# final_sensor_sch_v3.net
KiCad netlist of a schematic drawn in Altium Designer
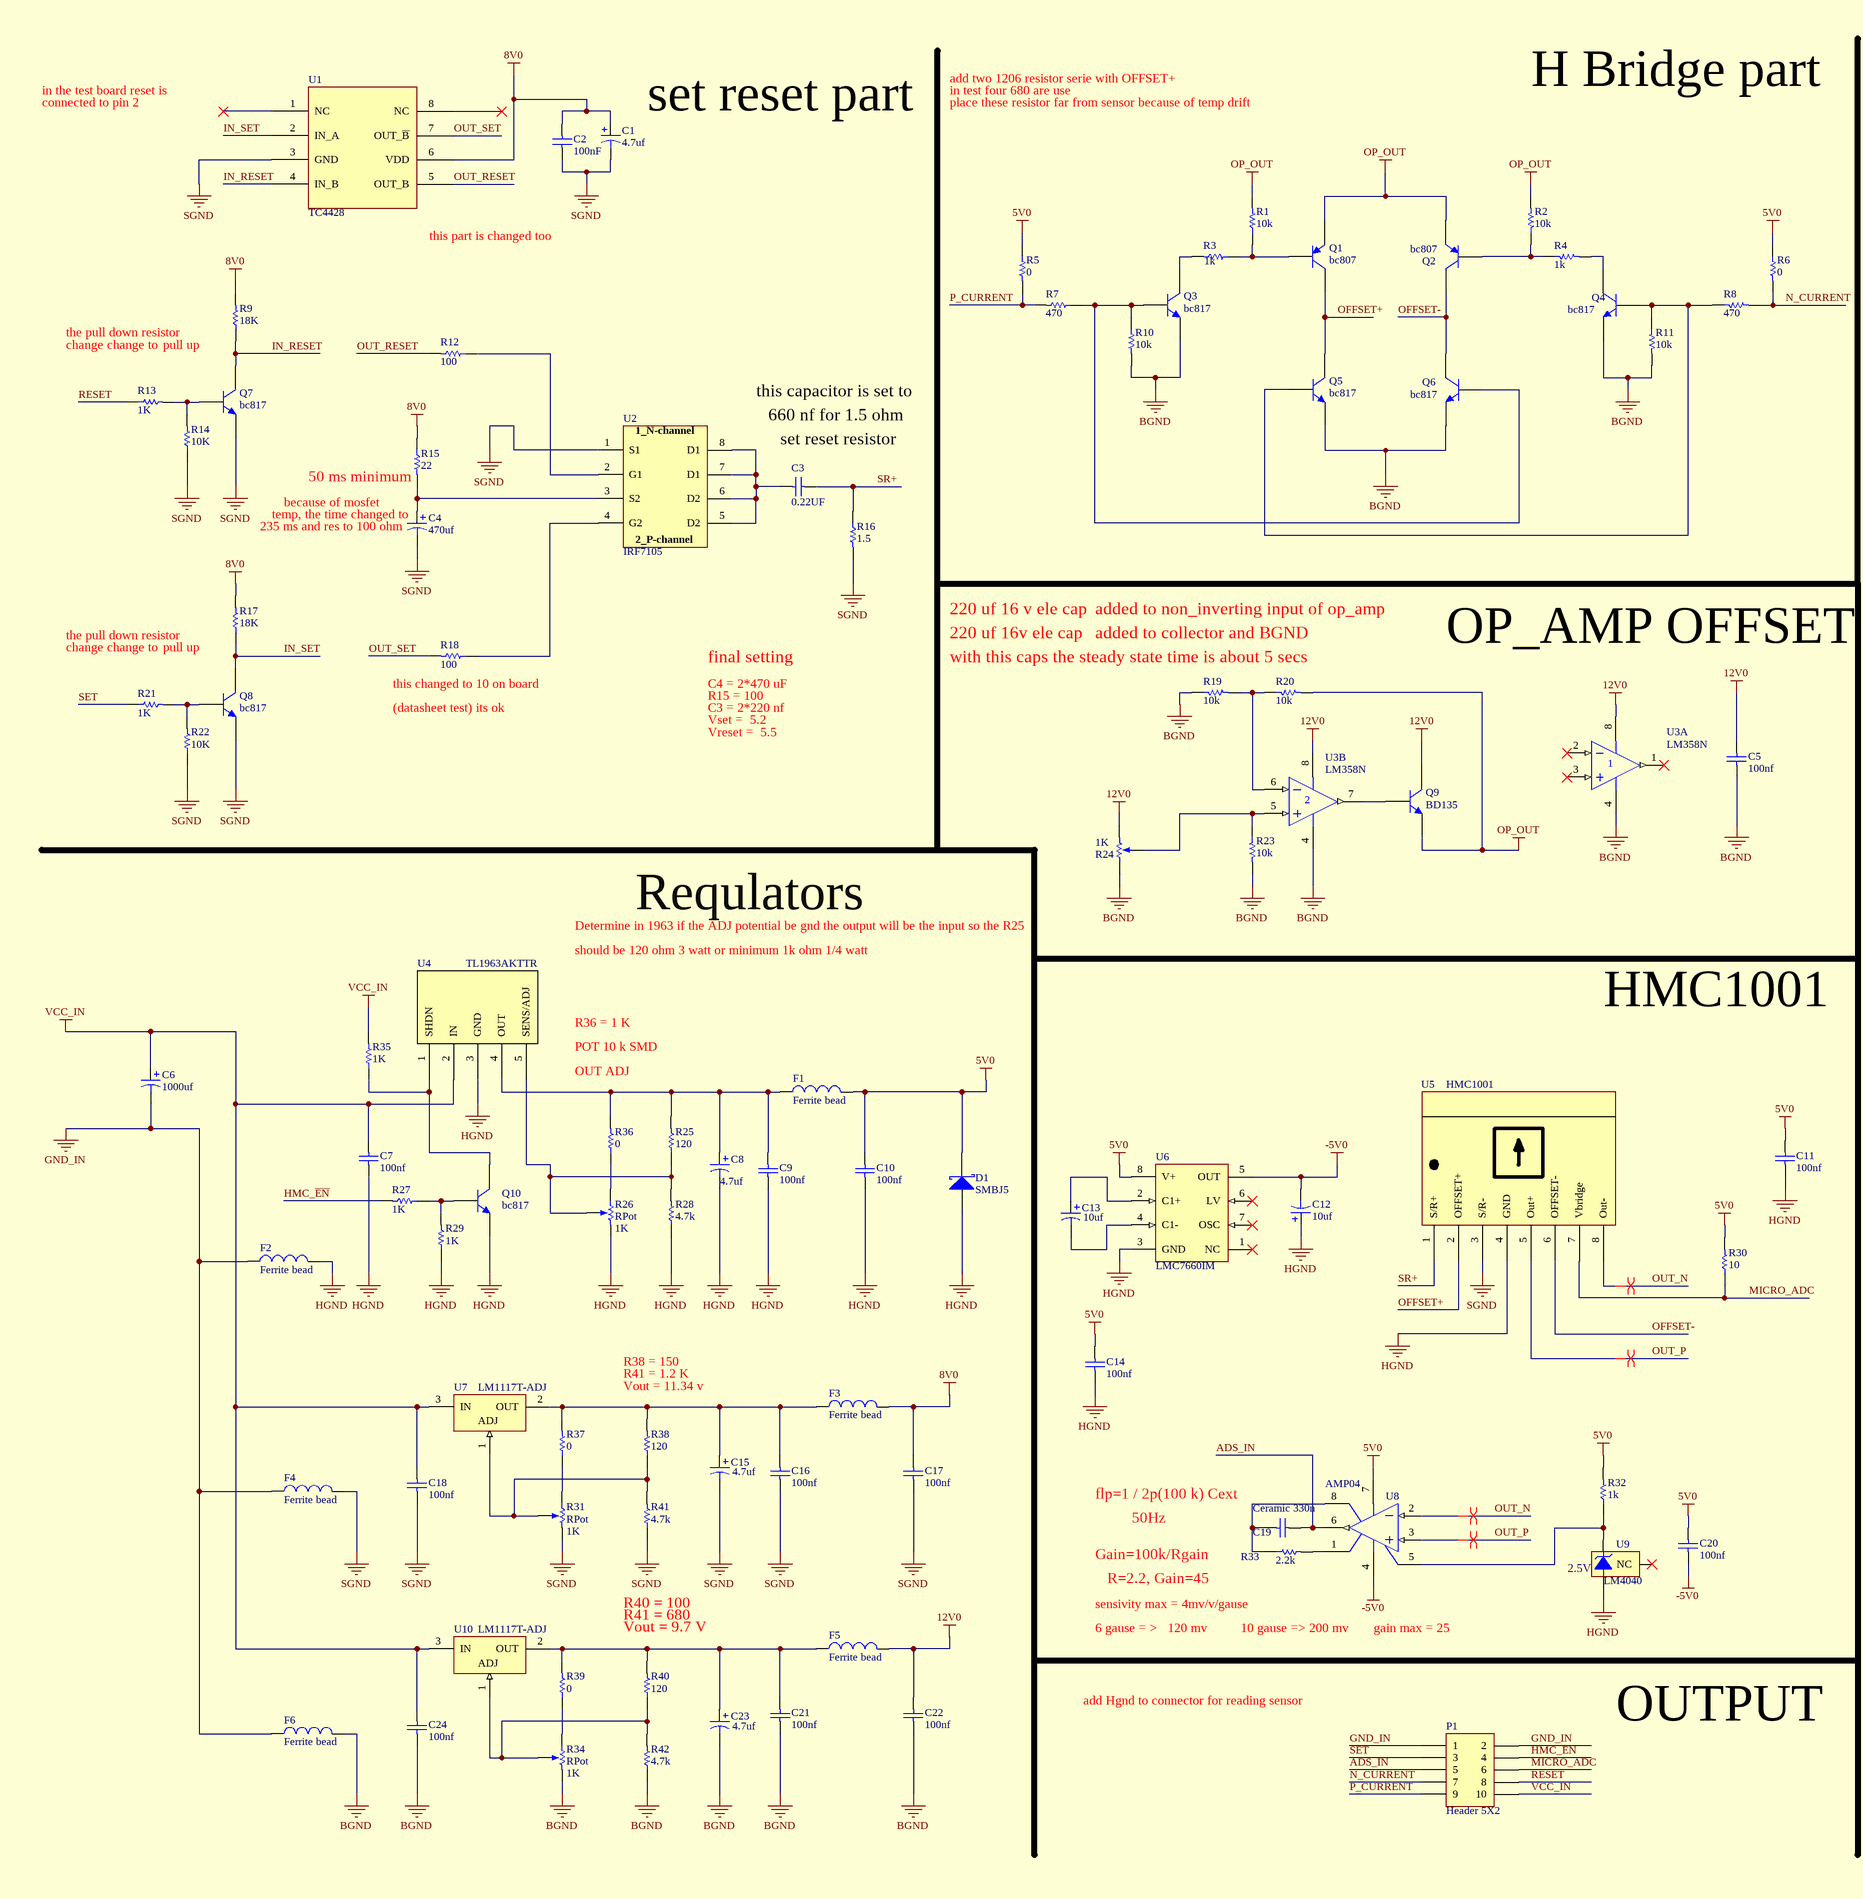
[diagram p0: final_sensor_sch_v3.SchDoc, left]
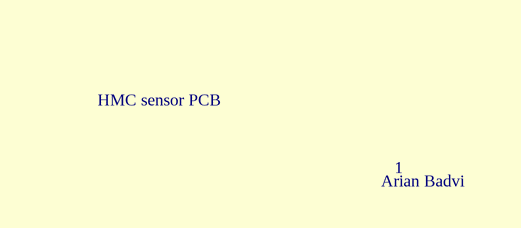
[diagram p1: final_sensor_sch_v3.SchDoc, right]

(export (version "E")
  (design (tool "Eeschema 10.0.6"))
  (components
    (comp (ref "C1")
      (value "4.7uf")
      (footprint "cap_smd_a")
      (description "Polarized Capacitor (Radial)")
      (fields (field (name "PUBLISHER") "Altium Limited"))
      (libsource (lib "") (part "Cap Pol1_1"))
    )
    (comp (ref "C2")
      (value "100nF")
      (footprint "1206")
      (description "Capacitor")
      (fields (field (name "PUBLISHER") "Altium Limited"))
      (libsource (lib "Miscellaneous Devices") (part "Cap"))
    )
    (comp (ref "C3")
      (value "0.22UF")
      (footprint "1206")
      (description "Capacitor")
      (fields (field (name "PUBLISHER") "Altium Limited"))
      (libsource (lib "Miscellaneous Devices") (part "Cap"))
    )
    (comp (ref "C4")
      (value "470uf")
      (footprint "cap_smd_d")
      (description "Polarized Capacitor (Radial)")
      (fields (field (name "PUBLISHER") "Altium Limited"))
      (libsource (lib "Miscellaneous Devices") (part "Cap Pol1"))
    )
    (comp (ref "C5")
      (value "100nf")
      (footprint "1206")
      (description "Capacitor")
      (fields (field (name "PUBLISHER") "Altium Limited"))
      (libsource (lib "Miscellaneous Devices") (part "Cap"))
    )
    (comp (ref "C6")
      (value "1000uf")
      (footprint "c_cyl_smd")
      (description "electrolytic smd cap")
      (fields (field (name "PUBLISHER") "Altium Limited"))
      (libsource (lib "Miscellaneous Devices") (part "Cap Pol1"))
    )
    (comp (ref "C7")
      (value "100nf")
      (footprint "1206")
      (description "Capacitor")
      (fields (field (name "PUBLISHER") "Altium Limited"))
      (libsource (lib "Miscellaneous Devices") (part "Cap"))
    )
    (comp (ref "C8")
      (value "4.7uf")
      (footprint "cap_smd_a")
      (description "Polarized Capacitor (Radial)")
      (fields (field (name "PUBLISHER") "Altium Limited"))
      (libsource (lib "Miscellaneous Devices") (part "Cap Pol1"))
    )
    (comp (ref "C9")
      (value "100nf")
      (footprint "1206")
      (description "Capacitor")
      (fields (field (name "PUBLISHER") "Altium Limited"))
      (libsource (lib "Miscellaneous Devices") (part "Cap"))
    )
    (comp (ref "C10")
      (value "100nf")
      (footprint "1206")
      (description "Capacitor")
      (fields (field (name "PUBLISHER") "Altium Limited"))
      (libsource (lib "Miscellaneous Devices") (part "Cap"))
    )
    (comp (ref "C11")
      (value "100nf")
      (footprint "1206")
      (description "Capacitor")
      (fields (field (name "PUBLISHER") "Altium Limited"))
      (libsource (lib "Miscellaneous Devices") (part "Cap"))
    )
    (comp (ref "C12")
      (value "10uf")
      (footprint "cap_smd_a")
      (description "Polarized Capacitor (Radial)")
      (fields (field (name "PUBLISHER") "Altium Limited"))
      (libsource (lib "Miscellaneous Devices") (part "Cap Pol1"))
    )
    (comp (ref "C13")
      (value "10uf")
      (footprint "cap_smd_a")
      (description "Polarized Capacitor (Radial)")
      (fields (field (name "PUBLISHER") "Altium Limited"))
      (libsource (lib "Miscellaneous Devices") (part "Cap Pol1"))
    )
    (comp (ref "C14")
      (value "100nf")
      (footprint "1206")
      (description "Capacitor")
      (fields (field (name "PUBLISHER") "Altium Limited"))
      (libsource (lib "Miscellaneous Devices") (part "Cap"))
    )
    (comp (ref "C15")
      (value "4.7uf")
      (footprint "cap_smd_a")
      (description "Polarized Capacitor (Radial)")
      (fields (field (name "PUBLISHER") "Altium Limited"))
      (libsource (lib "Miscellaneous Devices") (part "Cap Pol1"))
    )
    (comp (ref "C16")
      (value "100nf")
      (footprint "1206")
      (description "Capacitor")
      (fields (field (name "PUBLISHER") "Altium Limited"))
      (libsource (lib "Miscellaneous Devices") (part "Cap"))
    )
    (comp (ref "C17")
      (value "100nf")
      (footprint "1206")
      (description "Capacitor")
      (fields (field (name "PUBLISHER") "Altium Limited"))
      (libsource (lib "Miscellaneous Devices") (part "Cap"))
    )
    (comp (ref "C18")
      (value "100nf")
      (footprint "1206")
      (description "Capacitor")
      (fields (field (name "PUBLISHER") "Altium Limited"))
      (libsource (lib "Miscellaneous Devices") (part "Cap"))
    )
    (comp (ref "C19")
      (value "Ceramic 330n")
      (footprint "1206")
      (description "Capacitor")
      (fields (field (name "PUBLISHER") "Altium Limited"))
      (libsource (lib "Library") (part "Cap"))
    )
    (comp (ref "C20")
      (value "100nf")
      (footprint "1206")
      (description "Capacitor")
      (fields (field (name "PUBLISHER") "Altium Limited"))
      (libsource (lib "Miscellaneous Devices") (part "Cap"))
    )
    (comp (ref "C21")
      (value "100nf")
      (footprint "1206")
      (description "Capacitor")
      (fields (field (name "PUBLISHER") "Altium Limited"))
      (libsource (lib "Miscellaneous Devices") (part "Cap"))
    )
    (comp (ref "C22")
      (value "100nf")
      (footprint "1206")
      (description "Capacitor")
      (fields (field (name "PUBLISHER") "Altium Limited"))
      (libsource (lib "Miscellaneous Devices") (part "Cap"))
    )
    (comp (ref "C23")
      (value "4.7uf")
      (footprint "cap_smd_a")
      (description "Polarized Capacitor (Radial)")
      (fields (field (name "PUBLISHER") "Altium Limited"))
      (libsource (lib "Miscellaneous Devices") (part "Cap Pol1"))
    )
    (comp (ref "C24")
      (value "100nf")
      (footprint "1206")
      (description "Capacitor")
      (fields (field (name "PUBLISHER") "Altium Limited"))
      (libsource (lib "Miscellaneous Devices") (part "Cap"))
    )
    (comp (ref "D1")
      (value "SMBJ5")
      (footprint "tvs")
      (description "tvs")
      (fields (field (name "PUBLISHER") "Altium Limited"))
      (libsource (lib "Miscellaneous Devices") (part "Diode 10TQ040"))
    )
    (comp (ref "F1")
      (value "Ferrite bead")
      (footprint "1206")
      (description "Ferrite bead, 1206")
      (fields (field (name "PUBLISHER") "Altium Limited"))
      (libsource (lib "Miscellaneous Devices") (part "Inductor"))
    )
    (comp (ref "F2")
      (value "Ferrite bead")
      (footprint "1206")
      (description "Ferrite bead, 1206")
      (fields (field (name "PUBLISHER") "Altium Limited"))
      (libsource (lib "Miscellaneous Devices") (part "Inductor"))
    )
    (comp (ref "F3")
      (value "Ferrite bead")
      (footprint "1206")
      (description "Ferrite bead, 1206")
      (fields (field (name "PUBLISHER") "Altium Limited"))
      (libsource (lib "Miscellaneous Devices") (part "Inductor"))
    )
    (comp (ref "F4")
      (value "Ferrite bead")
      (footprint "1206")
      (description "Ferrite bead, 1206")
      (fields (field (name "PUBLISHER") "Altium Limited"))
      (libsource (lib "Miscellaneous Devices") (part "Inductor"))
    )
    (comp (ref "F5")
      (value "Ferrite bead")
      (footprint "1206")
      (description "Ferrite bead, 1206")
      (fields (field (name "PUBLISHER") "Altium Limited"))
      (libsource (lib "Miscellaneous Devices") (part "Inductor"))
    )
    (comp (ref "F6")
      (value "Ferrite bead")
      (footprint "1206")
      (description "Ferrite bead, 1206")
      (fields (field (name "PUBLISHER") "Altium Limited"))
      (libsource (lib "Miscellaneous Devices") (part "Inductor"))
    )
    (comp (ref "P1")
      (value "Header 5X2")
      (footprint "HDR2X5")
      (description "Header, 5-Pin, Dual row")
      (fields (field (name "PUBLISHER") "Altium Limited"))
      (libsource (lib "Miscellaneous Connectors") (part "Header 5X2"))
    )
    (comp (ref "Q1")
      (value "bc807")
      (footprint "sot-23")
      (description "PNP General Purpose Amplifier")
      (fields (field (name "PUBLISHER") "Altium Limited"))
      (libsource (lib "Miscellaneous Devices") (part "2N3906"))
    )
    (comp (ref "Q2")
      (value "bc807")
      (footprint "sot-23")
      (description "PNP General Purpose Amplifier")
      (fields (field (name "PUBLISHER") "Altium Limited"))
      (libsource (lib "Miscellaneous Devices") (part "2N3906"))
    )
    (comp (ref "Q3")
      (value "bc817")
      (footprint "sot-23")
      (description "NPN General Purpose Amplifier")
      (fields (field (name "PUBLISHER") "Altium Limited"))
      (libsource (lib "Miscellaneous Devices") (part "2N3904"))
    )
    (comp (ref "Q4")
      (value "bc817")
      (footprint "sot-23")
      (description "NPN General Purpose Amplifier")
      (fields (field (name "PUBLISHER") "Altium Limited"))
      (libsource (lib "Miscellaneous Devices") (part "2N3904"))
    )
    (comp (ref "Q5")
      (value "bc817")
      (footprint "sot-23")
      (description "NPN General Purpose Amplifier")
      (fields (field (name "PUBLISHER") "Altium Limited"))
      (libsource (lib "Miscellaneous Devices") (part "2N3904"))
    )
    (comp (ref "Q6")
      (value "bc817")
      (footprint "sot-23")
      (description "NPN General Purpose Amplifier")
      (fields (field (name "PUBLISHER") "Altium Limited"))
      (libsource (lib "Miscellaneous Devices") (part "2N3904"))
    )
    (comp (ref "Q7")
      (value "bc817")
      (footprint "sot-23")
      (description "NPN General Purpose Amplifier")
      (fields (field (name "PUBLISHER") "Altium Limited"))
      (libsource (lib "Miscellaneous Devices") (part "2N3904"))
    )
    (comp (ref "Q8")
      (value "bc817")
      (footprint "sot-23")
      (description "NPN General Purpose Amplifier")
      (fields (field (name "PUBLISHER") "Altium Limited"))
      (libsource (lib "Miscellaneous Devices") (part "2N3904"))
    )
    (comp (ref "Q9")
      (value "BD135")
      (footprint "sot-32")
      (description "NPN General Purpose Amplifier")
      (fields (field (name "PUBLISHER") "Altium Limited"))
      (libsource (lib "") (part "2N3904_1"))
    )
    (comp (ref "Q10")
      (value "bc817")
      (footprint "sot-23")
      (description "NPN General Purpose Amplifier")
      (fields (field (name "PUBLISHER") "Altium Limited"))
      (libsource (lib "Miscellaneous Devices") (part "2N3904"))
    )
    (comp (ref "R1")
      (value "10k")
      (footprint "1206")
      (description "Resistor")
      (fields (field (name "PUBLISHER") "Altium Limited"))
      (libsource (lib "Miscellaneous Devices") (part "Res1"))
    )
    (comp (ref "R2")
      (value "10k")
      (footprint "1206")
      (description "Resistor")
      (fields (field (name "PUBLISHER") "Altium Limited"))
      (libsource (lib "Miscellaneous Devices") (part "Res1"))
    )
    (comp (ref "R3")
      (value "1k")
      (footprint "1206")
      (description "Resistor")
      (fields (field (name "PUBLISHER") "Altium Limited"))
      (libsource (lib "Miscellaneous Devices") (part "Res1"))
    )
    (comp (ref "R4")
      (value "1k")
      (footprint "1206")
      (description "Resistor")
      (fields (field (name "PUBLISHER") "Altium Limited"))
      (libsource (lib "Miscellaneous Devices") (part "Res1"))
    )
    (comp (ref "R5")
      (value "0")
      (footprint "1206")
      (description "Resistor")
      (fields (field (name "PUBLISHER") "Altium Limited"))
      (libsource (lib "Miscellaneous Devices") (part "Res1"))
    )
    (comp (ref "R6")
      (value "0")
      (footprint "1206")
      (description "Resistor")
      (fields (field (name "PUBLISHER") "Altium Limited"))
      (libsource (lib "Miscellaneous Devices") (part "Res1"))
    )
    (comp (ref "R7")
      (value "470")
      (footprint "1206")
      (description "Resistor")
      (fields (field (name "PUBLISHER") "Altium Limited"))
      (libsource (lib "Miscellaneous Devices") (part "Res1"))
    )
    (comp (ref "R8")
      (value "470")
      (footprint "1206")
      (description "Resistor")
      (fields (field (name "PUBLISHER") "Altium Limited"))
      (libsource (lib "Miscellaneous Devices") (part "Res1"))
    )
    (comp (ref "R9")
      (value "18K")
      (footprint "1206")
      (description "Resistor")
      (fields (field (name "PUBLISHER") "Altium Limited"))
      (libsource (lib "Miscellaneous Devices") (part "Res1"))
    )
    (comp (ref "R10")
      (value "10k")
      (footprint "1206")
      (description "Resistor")
      (fields (field (name "PUBLISHER") "Altium Limited"))
      (libsource (lib "Miscellaneous Devices") (part "Res1"))
    )
    (comp (ref "R11")
      (value "10k")
      (footprint "1206")
      (description "Resistor")
      (fields (field (name "PUBLISHER") "Altium Limited"))
      (libsource (lib "Miscellaneous Devices") (part "Res1"))
    )
    (comp (ref "R12")
      (value "100")
      (footprint "1206")
      (description "Resistor")
      (fields (field (name "PUBLISHER") "Altium Limited"))
      (libsource (lib "Miscellaneous Devices") (part "Res1"))
    )
    (comp (ref "R13")
      (value "1K")
      (footprint "1206")
      (description "Resistor")
      (fields (field (name "PUBLISHER") "Altium Limited"))
      (libsource (lib "Miscellaneous Devices") (part "Res1"))
    )
    (comp (ref "R14")
      (value "10K")
      (footprint "1206")
      (description "Resistor")
      (fields (field (name "PUBLISHER") "Altium Limited"))
      (libsource (lib "Miscellaneous Devices") (part "Res1"))
    )
    (comp (ref "R15")
      (value "22")
      (footprint "1206")
      (description "Resistor")
      (fields (field (name "PUBLISHER") "Altium Limited"))
      (libsource (lib "Miscellaneous Devices") (part "Res1"))
    )
    (comp (ref "R16")
      (value "1.5")
      (footprint "1206")
      (description "Resistor")
      (fields (field (name "PUBLISHER") "Altium Limited"))
      (libsource (lib "Miscellaneous Devices") (part "Res1"))
    )
    (comp (ref "R17")
      (value "18K")
      (footprint "1206")
      (description "Resistor")
      (fields (field (name "PUBLISHER") "Altium Limited"))
      (libsource (lib "Miscellaneous Devices") (part "Res1"))
    )
    (comp (ref "R18")
      (value "100")
      (footprint "1206")
      (description "Resistor")
      (fields (field (name "PUBLISHER") "Altium Limited"))
      (libsource (lib "Miscellaneous Devices") (part "Res1"))
    )
    (comp (ref "R19")
      (value "10k")
      (footprint "1206")
      (description "Resistor")
      (fields (field (name "PUBLISHER") "Altium Limited"))
      (libsource (lib "") (part "Res1_1"))
    )
    (comp (ref "R20")
      (value "10k")
      (footprint "1206")
      (description "Resistor")
      (fields (field (name "PUBLISHER") "Altium Limited"))
      (libsource (lib "") (part "Res1_1"))
    )
    (comp (ref "R21")
      (value "1K")
      (footprint "1206")
      (description "Resistor")
      (fields (field (name "PUBLISHER") "Altium Limited"))
      (libsource (lib "Miscellaneous Devices") (part "Res1"))
    )
    (comp (ref "R22")
      (value "10K")
      (footprint "1206")
      (description "Resistor")
      (fields (field (name "PUBLISHER") "Altium Limited"))
      (libsource (lib "Miscellaneous Devices") (part "Res1"))
    )
    (comp (ref "R23")
      (value "10k")
      (footprint "1206")
      (description "Resistor")
      (fields (field (name "PUBLISHER") "Altium Limited"))
      (libsource (lib "Miscellaneous Devices") (part "Res1"))
    )
    (comp (ref "R24")
      (value "1K")
      (footprint "pot smd")
      (description "Potentiometer")
      (fields (field (name "Comment") "RPot") (field (name "PUBLISHER") "Altium Limited"))
      (libsource (lib "Miscellaneous Devices") (part "RPot"))
    )
    (comp (ref "R25")
      (value "120")
      (footprint "1206")
      (description "Resistor, 1/4W")
      (fields (field (name "PUBLISHER") "Seyed Razi Vesali") (field (name "EMAIL") "razi.vesali@gmail.com"))
      (libsource (lib "resistor1") (part "Resistor"))
    )
    (comp (ref "R26")
      (value "RPot")
      (footprint "pot smd")
      (description "Potentiometer")
      (fields (field (name "ALTIUM_VALUE") "1K") (field (name "PUBLISHER") "Altium Limited"))
      (libsource (lib "Miscellaneous Devices") (part "RPot"))
    )
    (comp (ref "R27")
      (value "1K")
      (footprint "1206")
      (description "Resistor")
      (fields (field (name "PUBLISHER") "Altium Limited"))
      (libsource (lib "Miscellaneous Devices") (part "Res1"))
    )
    (comp (ref "R28")
      (value "4.7k")
      (footprint "1206")
      (description "Resistor, 1/4W")
      (fields (field (name "PUBLISHER") "Seyed Razi Vesali") (field (name "EMAIL") "razi.vesali@gmail.com"))
      (libsource (lib "resistor1") (part "Resistor"))
    )
    (comp (ref "R29")
      (value "1K")
      (footprint "1206")
      (description "Resistor")
      (fields (field (name "PUBLISHER") "Altium Limited"))
      (libsource (lib "Miscellaneous Devices") (part "Res1"))
    )
    (comp (ref "R30")
      (value "10")
      (footprint "1206")
      (description "Resistor, 1/4W")
      (fields (field (name "PUBLISHER") "Seyed Razi Vesali") (field (name "EMAIL") "razi.vesali@gmail.com"))
      (libsource (lib "resistor1") (part "Resistor"))
    )
    (comp (ref "R31")
      (value "RPot")
      (footprint "pot smd")
      (description "Potentiometer")
      (fields (field (name "ALTIUM_VALUE") "1K") (field (name "PUBLISHER") "Altium Limited"))
      (libsource (lib "") (part "RPot_1"))
    )
    (comp (ref "R32")
      (value "1k")
      (footprint "1206")
      (description "Resistor, 1/4W")
      (fields (field (name "PUBLISHER") "Seyed Razi Vesali") (field (name "EMAIL") "razi.vesali@gmail.com"))
      (libsource (lib "resistor1") (part "Resistor"))
    )
    (comp (ref "R33")
      (value "2.2k")
      (footprint "1206")
      (description "General Resistor")
      (fields (field (name "PUBLISHER") "Altium Limited"))
      (libsource (lib "Library") (part "Resistor"))
    )
    (comp (ref "R34")
      (value "RPot")
      (footprint "pot smd")
      (description "Potentiometer")
      (fields (field (name "ALTIUM_VALUE") "1K") (field (name "PUBLISHER") "Altium Limited"))
      (libsource (lib "") (part "RPot_1"))
    )
    (comp (ref "R35")
      (value "1K")
      (footprint "1206")
      (description "Resistor")
      (fields (field (name "PUBLISHER") "Altium Limited"))
      (libsource (lib "Miscellaneous Devices") (part "Res1"))
    )
    (comp (ref "R36")
      (value "0")
      (footprint "1206")
      (description "Resistor, 1/4W")
      (fields (field (name "PUBLISHER") "Seyed Razi Vesali") (field (name "EMAIL") "razi.vesali@gmail.com"))
      (libsource (lib "resistor1") (part "Resistor"))
    )
    (comp (ref "R37")
      (value "0")
      (footprint "1206")
      (description "Resistor, 1/4W")
      (fields (field (name "PUBLISHER") "Seyed Razi Vesali") (field (name "EMAIL") "razi.vesali@gmail.com"))
      (libsource (lib "resistor1") (part "Resistor"))
    )
    (comp (ref "R38")
      (value "120")
      (footprint "1206")
      (description "Resistor, 1/4W")
      (fields (field (name "PUBLISHER") "Seyed Razi Vesali") (field (name "EMAIL") "razi.vesali@gmail.com"))
      (libsource (lib "resistor1") (part "Resistor"))
    )
    (comp (ref "R39")
      (value "0")
      (footprint "1206")
      (description "Resistor, 1/4W")
      (fields (field (name "PUBLISHER") "Seyed Razi Vesali") (field (name "EMAIL") "razi.vesali@gmail.com"))
      (libsource (lib "resistor1") (part "Resistor"))
    )
    (comp (ref "R40")
      (value "120")
      (footprint "1206")
      (description "Resistor, 1/4W")
      (fields (field (name "PUBLISHER") "Seyed Razi Vesali") (field (name "EMAIL") "razi.vesali@gmail.com"))
      (libsource (lib "resistor1") (part "Resistor"))
    )
    (comp (ref "R41")
      (value "4.7k")
      (footprint "1206")
      (description "Resistor, 1/4W")
      (fields (field (name "PUBLISHER") "Seyed Razi Vesali") (field (name "EMAIL") "razi.vesali@gmail.com"))
      (libsource (lib "resistor1") (part "Resistor"))
    )
    (comp (ref "R42")
      (value "4.7k")
      (footprint "1206")
      (description "Resistor, 1/4W")
      (fields (field (name "PUBLISHER") "Seyed Razi Vesali") (field (name "EMAIL") "razi.vesali@gmail.com"))
      (libsource (lib "resistor1") (part "Resistor"))
    )
    (comp (ref "U1") (value "TC4428") (footprint "sop8") (libsource (lib "tc4428") (part "TC4428")))
    (comp (ref "U2") (value "IRF7105") (footprint "sop8") (libsource (lib "irf7106") (part "IRF7106")))
    (comp (ref "U3")
      (value "LM358N")
      (footprint "sop8")
      (description "Dual Low-Power Operational Amplifier")
      (fields (field (name "PUBLISHER") "Altium Limited"))
      (libsource (lib "Motorola Amplifier Operational Amplifier") (part "LM358N"))
    )
    (comp (ref "U4") (value "TL1963AKTTR") (footprint "tl1963") (libsource (lib "Library") (part "TL1963")))
    (comp (ref "U5") (value "HMC1001") (footprint "HMC1001") (libsource (lib "Library") (part "HMC1001")))
    (comp (ref "U6")
      (value "LMC7660IM")
      (footprint "sop8")
      (description "Switched Capacitor Voltage Converter")
      (fields
        (field (name "MANUFACTURER") "National Semiconductor")
        (field (name "DIGIKEYPARTNUMBER") "LMC7660IM-ND")
        (field (name "PUBLISHER") "Altium Limited")
      )
      (libsource (lib "NSC Switch Caps") (part "LMC7660IM"))
    )
    (comp (ref "U7")
      (value "LM1117T-ADJ")
      (footprint "dpak")
      (description "800mA Low-Dropout Linear Regulator")
      (fields
        (field (name "MANUFACTURER") "National Semiconductor")
        (field (name "DIGIKEYPARTNUMBER") "LM1117T-ADJ-ND")
        (field (name "PUBLISHER") "Altium Limited")
      )
      (libsource (lib "NSC LDO") (part "LM1117T-ADJ"))
    )
    (comp (ref "U8")
      (value "AMP04")
      (footprint "sop8")
      (fields (field (name "PUBLISHER") "Altium Limited"))
      (libsource (lib "Miscellaneous Devices") (part "Op Amp"))
    )
    (comp (ref "U9")
      (value "LM4040")
      (footprint "sot-23")
      (description "Precision Micropower Shunt Voltage Reference, 3-pin SOT-23")
      (fields
        (field (name "PARTNUMBER") "LM4040DIM3-10.0")
        (field (name "MANUFACTURER") "National Semiconductor")
        (field (name "PUBLISHER") "Altium Limited")
      )
      (libsource (lib "final_sensor_sch_lib") (part "LM4040"))
    )
    (comp (ref "U10")
      (value "LM1117T-ADJ")
      (footprint "dpak")
      (description "800mA Low-Dropout Linear Regulator")
      (fields
        (field (name "MANUFACTURER") "National Semiconductor")
        (field (name "DIGIKEYPARTNUMBER") "LM1117T-ADJ-ND")
        (field (name "PUBLISHER") "Altium Limited")
      )
      (libsource (lib "NSC LDO") (part "LM1117T-ADJ"))
    )
  )
  (nets
    (net (code "1") (name "-5V0") (class "Default")
      (node (ref "C12") (pin "2") (pinfunction "2_2") (pintype "passive"))
      (node (ref "C20") (pin "1") (pinfunction "1_1") (pintype "passive"))
      (node (ref "U6") (pin "5") (pinfunction "OUT_5") (pintype "power_in"))
      (node (ref "U8") (pin "4") (pinfunction "V-_4") (pintype "power_in"))
    )
    (net (code "2") (name "/ADS_IN") (class "Default")
      (node (ref "C19") (pin "1") (pinfunction "1_1") (pintype "passive"))
      (node (ref "P1") (pin "5") (pinfunction "5_5") (pintype "passive"))
      (node (ref "U8") (pin "6") (pinfunction "OUT_6") (pintype "output"))
    )
    (net (code "3") (name "/HMC_~{EN}") (class "Default")
      (node (ref "P1") (pin "4") (pinfunction "4_4") (pintype "passive"))
      (node (ref "R27") (pin "2") (pinfunction "2_2") (pintype "passive"))
    )
    (net (code "4") (name "/IN_RESET") (class "Default")
      (node (ref "Q7") (pin "3") (pinfunction "C_3") (pintype "passive"))
      (node (ref "R9") (pin "1") (pinfunction "1_1") (pintype "passive"))
      (node (ref "U1") (pin "4") (pinfunction "IN_B_4") (pintype "passive"))
    )
    (net (code "5") (name "/IN_SET") (class "Default")
      (node (ref "Q8") (pin "3") (pinfunction "C_3") (pintype "passive"))
      (node (ref "R17") (pin "1") (pinfunction "1_1") (pintype "passive"))
      (node (ref "U1") (pin "2") (pinfunction "IN_A_2") (pintype "passive"))
    )
    (net (code "6") (name "/MICRO_ADC") (class "Default")
      (node (ref "P1") (pin "6") (pinfunction "6_6") (pintype "passive"))
      (node (ref "R30") (pin "1") (pinfunction "1_1") (pintype "passive"))
      (node (ref "U5") (pin "7") (pinfunction "Vbridge_7") (pintype "passive"))
    )
    (net (code "7") (name "/N_CURRENT") (class "Default")
      (node (ref "P1") (pin "7") (pinfunction "7_7") (pintype "passive"))
      (node (ref "R6") (pin "2") (pinfunction "2_2") (pintype "passive"))
      (node (ref "R8") (pin "2") (pinfunction "2_2") (pintype "passive"))
    )
    (net (code "8") (name "/OFFSET+") (class "Default")
      (node (ref "Q1") (pin "3") (pinfunction "C_3") (pintype "passive"))
      (node (ref "Q5") (pin "3") (pinfunction "C_3") (pintype "passive"))
      (node (ref "U5") (pin "2") (pinfunction "OFFSET+_2") (pintype "passive"))
    )
    (net (code "9") (name "/OFFSET-") (class "Default")
      (node (ref "Q2") (pin "3") (pinfunction "C_3") (pintype "passive"))
      (node (ref "Q6") (pin "3") (pinfunction "C_3") (pintype "passive"))
      (node (ref "U5") (pin "6") (pinfunction "OFFSET-_6") (pintype "passive"))
    )
    (net (code "10") (name "/OUT_N") (class "Default")
      (node (ref "U5") (pin "8") (pinfunction "Out-_8") (pintype "passive"))
      (node (ref "U8") (pin "2") (pinfunction "IN-_2") (pintype "input"))
    )
    (net (code "11") (name "/OUT_P") (class "Default")
      (node (ref "U5") (pin "5") (pinfunction "Out+_5") (pintype "passive"))
      (node (ref "U8") (pin "3") (pinfunction "IN+_3") (pintype "input"))
    )
    (net (code "12") (name "/OUT_RESET") (class "Default")
      (node (ref "R12") (pin "2") (pinfunction "2_2") (pintype "passive"))
      (node (ref "U1") (pin "5") (pinfunction "OUT_B_5") (pintype "passive"))
    )
    (net (code "13") (name "/OUT_SET") (class "Default")
      (node (ref "R18") (pin "2") (pinfunction "2_2") (pintype "passive"))
      (node (ref "U1") (pin "7") (pinfunction "OUT_~{B}_7") (pintype "passive"))
    )
    (net (code "14") (name "/P_CURRENT") (class "Default")
      (node (ref "P1") (pin "9") (pinfunction "9_9") (pintype "passive"))
      (node (ref "R5") (pin "2") (pinfunction "2_2") (pintype "passive"))
      (node (ref "R7") (pin "2") (pinfunction "2_2") (pintype "passive"))
    )
    (net (code "15") (name "/RESET") (class "Default")
      (node (ref "P1") (pin "8") (pinfunction "8_8") (pintype "passive"))
      (node (ref "R13") (pin "1") (pinfunction "1_1") (pintype "passive"))
    )
    (net (code "16") (name "/SET") (class "Default")
      (node (ref "P1") (pin "3") (pinfunction "3_3") (pintype "passive"))
      (node (ref "R21") (pin "1") (pinfunction "1_1") (pintype "passive"))
    )
    (net (code "17") (name "/SR+") (class "Default")
      (node (ref "C3") (pin "2") (pinfunction "2_2") (pintype "passive"))
      (node (ref "R16") (pin "1") (pinfunction "1_1") (pintype "passive"))
      (node (ref "U5") (pin "1") (pinfunction "S/R+_1") (pintype "passive"))
    )
    (net (code "18") (name "5V0") (class "Default")
      (node (ref "C10") (pin "2") (pinfunction "2_2") (pintype "passive"))
      (node (ref "C11") (pin "2") (pinfunction "2_2") (pintype "passive"))
      (node (ref "C14") (pin "2") (pinfunction "2_2") (pintype "passive"))
      (node (ref "C20") (pin "2") (pinfunction "2_2") (pintype "passive"))
      (node (ref "D1") (pin "2") (pinfunction "K_2") (pintype "passive"))
      (node (ref "F1") (pin "2") (pinfunction "2_2") (pintype "passive"))
      (node (ref "R30") (pin "2") (pinfunction "2_2") (pintype "passive"))
      (node (ref "R32") (pin "2") (pinfunction "2_2") (pintype "passive"))
      (node (ref "R5") (pin "1") (pinfunction "1_1") (pintype "passive"))
      (node (ref "R6") (pin "1") (pinfunction "1_1") (pintype "passive"))
      (node (ref "U6") (pin "8") (pinfunction "V+_8") (pintype "power_in"))
      (node (ref "U8") (pin "7") (pinfunction "V+_7") (pintype "power_in"))
    )
    (net (code "19") (name "8V0") (class "Default")
      (node (ref "C1") (pin "1") (pinfunction "1_1") (pintype "passive"))
      (node (ref "C17") (pin "2") (pinfunction "2_2") (pintype "passive"))
      (node (ref "C2") (pin "1") (pinfunction "1_1") (pintype "passive"))
      (node (ref "F3") (pin "2") (pinfunction "2_2") (pintype "passive"))
      (node (ref "R15") (pin "1") (pinfunction "1_1") (pintype "passive"))
      (node (ref "R17") (pin "2") (pinfunction "2_2") (pintype "passive"))
      (node (ref "R9") (pin "2") (pinfunction "2_2") (pintype "passive"))
      (node (ref "U1") (pin "6") (pinfunction "VDD_6") (pintype "passive"))
    )
    (net (code "20") (name "12V0") (class "Default")
      (node (ref "C22") (pin "2") (pinfunction "2_2") (pintype "passive"))
      (node (ref "C5") (pin "2") (pinfunction "2_2") (pintype "passive"))
      (node (ref "F5") (pin "2") (pinfunction "2_2") (pintype "passive"))
      (node (ref "Q9") (pin "2") (pinfunction "C_2") (pintype "passive"))
      (node (ref "R24") (pin "3") (pinfunction "BOT_3") (pintype "passive"))
      (node (ref "U3") (pin "8") (pinfunction "V+_8") (pintype "power_in"))
    )
    (net (code "21") (name "BGND") (class "Default")
      (node (ref "C21") (pin "1") (pinfunction "1_1") (pintype "passive"))
      (node (ref "C22") (pin "1") (pinfunction "1_1") (pintype "passive"))
      (node (ref "C23") (pin "2") (pinfunction "2_2") (pintype "passive"))
      (node (ref "C24") (pin "1") (pinfunction "1_1") (pintype "passive"))
      (node (ref "C5") (pin "1") (pinfunction "1_1") (pintype "passive"))
      (node (ref "F6") (pin "2") (pinfunction "2_2") (pintype "passive"))
      (node (ref "Q3") (pin "2") (pinfunction "E_2") (pintype "passive"))
      (node (ref "Q4") (pin "2") (pinfunction "E_2") (pintype "passive"))
      (node (ref "Q5") (pin "2") (pinfunction "E_2") (pintype "passive"))
      (node (ref "Q6") (pin "2") (pinfunction "E_2") (pintype "passive"))
      (node (ref "R10") (pin "2") (pinfunction "2_2") (pintype "passive"))
      (node (ref "R11") (pin "2") (pinfunction "2_2") (pintype "passive"))
      (node (ref "R19") (pin "1") (pinfunction "1_1") (pintype "passive"))
      (node (ref "R23") (pin "2") (pinfunction "2_2") (pintype "passive"))
      (node (ref "R24") (pin "1") (pinfunction "TOP_1") (pintype "passive"))
      (node (ref "R34") (pin "2") (pinfunction "BOT_2") (pintype "passive"))
      (node (ref "R42") (pin "1") (pinfunction "1_1") (pintype "passive"))
      (node (ref "U3") (pin "4") (pinfunction "V-_4") (pintype "power_in"))
    )
    (net (code "22") (name "GND_IN") (class "Default")
      (node (ref "C6") (pin "2") (pinfunction "2_2") (pintype "passive"))
      (node (ref "F2") (pin "1") (pinfunction "1_1") (pintype "passive"))
      (node (ref "F4") (pin "1") (pinfunction "1_1") (pintype "passive"))
      (node (ref "F6") (pin "1") (pinfunction "1_1") (pintype "passive"))
      (node (ref "P1") (pin "1") (pinfunction "1_1") (pintype "passive"))
      (node (ref "P1") (pin "2") (pinfunction "2_2") (pintype "passive"))
    )
    (net (code "23") (name "HGND") (class "Default")
      (node (ref "C10") (pin "1") (pinfunction "1_1") (pintype "passive"))
      (node (ref "C11") (pin "1") (pinfunction "1_1") (pintype "passive"))
      (node (ref "C12") (pin "1") (pinfunction "1_1") (pintype "passive"))
      (node (ref "C14") (pin "1") (pinfunction "1_1") (pintype "passive"))
      (node (ref "C7") (pin "1") (pinfunction "1_1") (pintype "passive"))
      (node (ref "C8") (pin "2") (pinfunction "2_2") (pintype "passive"))
      (node (ref "C9") (pin "1") (pinfunction "1_1") (pintype "passive"))
      (node (ref "D1") (pin "1") (pinfunction "A_1") (pintype "passive"))
      (node (ref "F2") (pin "2") (pinfunction "2_2") (pintype "passive"))
      (node (ref "Q10") (pin "2") (pinfunction "E_2") (pintype "passive"))
      (node (ref "R26") (pin "3") (pinfunction "BOT_3") (pintype "passive"))
      (node (ref "R28") (pin "1") (pinfunction "1_1") (pintype "passive"))
      (node (ref "R29") (pin "1") (pinfunction "1_1") (pintype "passive"))
      (node (ref "U4") (pin "3") (pinfunction "GND_3") (pintype "passive"))
      (node (ref "U5") (pin "4") (pinfunction "GND_4") (pintype "passive"))
      (node (ref "U6") (pin "3") (pinfunction "GND_3") (pintype "power_in"))
      (node (ref "U9") (pin "2") (pinfunction "-V_2") (pintype "passive"))
    )
    (net (code "24") (name "Net-(C3-Pad1)") (class "Default")
      (node (ref "C3") (pin "1") (pinfunction "1_1") (pintype "passive"))
      (node (ref "U2") (pin "5") (pinfunction "D2_5") (pintype "passive"))
      (node (ref "U2") (pin "6") (pinfunction "D2_6") (pintype "passive"))
      (node (ref "U2") (pin "7") (pinfunction "D1_7") (pintype "passive"))
      (node (ref "U2") (pin "8") (pinfunction "D1_8") (pintype "passive"))
    )
    (net (code "25") (name "Net-(Q1-B)") (class "Default")
      (node (ref "Q1") (pin "1") (pinfunction "B_1") (pintype "passive"))
      (node (ref "R1") (pin "1") (pinfunction "1_1") (pintype "passive"))
      (node (ref "R3") (pin "1") (pinfunction "1_1") (pintype "passive"))
    )
    (net (code "26") (name "Net-(Q2-B)") (class "Default")
      (node (ref "Q2") (pin "1") (pinfunction "B_1") (pintype "passive"))
      (node (ref "R2") (pin "1") (pinfunction "1_1") (pintype "passive"))
      (node (ref "R4") (pin "1") (pinfunction "1_1") (pintype "passive"))
    )
    (net (code "27") (name "Net-(Q3-B)") (class "Default")
      (node (ref "Q3") (pin "1") (pinfunction "B_1") (pintype "passive"))
      (node (ref "Q6") (pin "1") (pinfunction "B_1") (pintype "passive"))
      (node (ref "R10") (pin "1") (pinfunction "1_1") (pintype "passive"))
      (node (ref "R7") (pin "1") (pinfunction "1_1") (pintype "passive"))
    )
    (net (code "28") (name "Net-(Q3-C)") (class "Default")
      (node (ref "Q3") (pin "3") (pinfunction "C_3") (pintype "passive"))
      (node (ref "R3") (pin "2") (pinfunction "2_2") (pintype "passive"))
    )
    (net (code "29") (name "Net-(Q4-B)") (class "Default")
      (node (ref "Q4") (pin "1") (pinfunction "B_1") (pintype "passive"))
      (node (ref "Q5") (pin "1") (pinfunction "B_1") (pintype "passive"))
      (node (ref "R11") (pin "1") (pinfunction "1_1") (pintype "passive"))
      (node (ref "R8") (pin "1") (pinfunction "1_1") (pintype "passive"))
    )
    (net (code "30") (name "Net-(Q4-C)") (class "Default")
      (node (ref "Q4") (pin "3") (pinfunction "C_3") (pintype "passive"))
      (node (ref "R4") (pin "2") (pinfunction "2_2") (pintype "passive"))
    )
    (net (code "31") (name "Net-(Q7-B)") (class "Default")
      (node (ref "Q7") (pin "1") (pinfunction "B_1") (pintype "passive"))
      (node (ref "R13") (pin "2") (pinfunction "2_2") (pintype "passive"))
      (node (ref "R14") (pin "2") (pinfunction "2_2") (pintype "passive"))
    )
    (net (code "32") (name "Net-(Q8-B)") (class "Default")
      (node (ref "Q8") (pin "1") (pinfunction "B_1") (pintype "passive"))
      (node (ref "R21") (pin "2") (pinfunction "2_2") (pintype "passive"))
      (node (ref "R22") (pin "2") (pinfunction "2_2") (pintype "passive"))
    )
    (net (code "33") (name "Net-(Q9-B)") (class "Default")
      (node (ref "Q9") (pin "1") (pinfunction "B_1") (pintype "passive"))
      (node (ref "U3") (pin "7") (pinfunction "OUT_7") (pintype "output"))
    )
    (net (code "34") (name "Net-(Q10-B)") (class "Default")
      (node (ref "Q10") (pin "1") (pinfunction "B_1") (pintype "passive"))
      (node (ref "R27") (pin "1") (pinfunction "1_1") (pintype "passive"))
      (node (ref "R29") (pin "2") (pinfunction "2_2") (pintype "passive"))
    )
    (net (code "35") (name "Net-(Q10-C)") (class "Default")
      (node (ref "Q10") (pin "3") (pinfunction "C_3") (pintype "passive"))
      (node (ref "R35") (pin "1") (pinfunction "1_1") (pintype "passive"))
      (node (ref "U4") (pin "1") (pinfunction "SHDN_1") (pintype "passive"))
    )
    (net (code "36") (name "Net-(R24-TAP)") (class "Default")
      (node (ref "R23") (pin "1") (pinfunction "1_1") (pintype "passive"))
      (node (ref "R24") (pin "2") (pinfunction "TAP_2") (pintype "passive"))
      (node (ref "U3") (pin "5") (pinfunction "IN+_5") (pintype "input"))
    )
    (net (code "37") (name "Net-(R26-TAP)") (class "Default")
      (node (ref "R25") (pin "1") (pinfunction "1_1") (pintype "passive"))
      (node (ref "R26") (pin "2") (pinfunction "TAP_2") (pintype "passive"))
      (node (ref "R28") (pin "2") (pinfunction "2_2") (pintype "passive"))
      (node (ref "U4") (pin "5") (pinfunction "SENS/ADJ_5") (pintype "passive"))
    )
    (net (code "38") (name "Net-(R26-TOP)") (class "Default")
      (node (ref "R26") (pin "1") (pinfunction "TOP_1") (pintype "passive"))
      (node (ref "R36") (pin "1") (pinfunction "1_1") (pintype "passive"))
    )
    (net (code "39") (name "Net-(R31-TAP)") (class "Default")
      (node (ref "R31") (pin "3") (pinfunction "TAP_3") (pintype "passive"))
      (node (ref "R38") (pin "1") (pinfunction "1_1") (pintype "passive"))
      (node (ref "R41") (pin "2") (pinfunction "2_2") (pintype "passive"))
      (node (ref "U7") (pin "1") (pinfunction "ADJ_1") (pintype "input"))
    )
    (net (code "40") (name "Net-(R31-TOP)") (class "Default")
      (node (ref "R31") (pin "1") (pinfunction "TOP_1") (pintype "passive"))
      (node (ref "R37") (pin "1") (pinfunction "1_1") (pintype "passive"))
    )
    (net (code "41") (name "Net-(R33-Pad2)") (class "Default")
      (node (ref "R33") (pin "2") (pinfunction "2_2") (pintype "passive"))
      (node (ref "U8") (pin "1") (pinfunction "OS_NUL_1") (pintype "passive"))
    )
    (net (code "42") (name "Net-(R34-TAP)") (class "Default")
      (node (ref "R34") (pin "3") (pinfunction "TAP_3") (pintype "passive"))
      (node (ref "R40") (pin "1") (pinfunction "1_1") (pintype "passive"))
      (node (ref "R42") (pin "2") (pinfunction "2_2") (pintype "passive"))
      (node (ref "U10") (pin "1") (pinfunction "ADJ_1") (pintype "input"))
    )
    (net (code "43") (name "Net-(R34-TOP)") (class "Default")
      (node (ref "R34") (pin "1") (pinfunction "TOP_1") (pintype "passive"))
      (node (ref "R39") (pin "1") (pinfunction "1_1") (pintype "passive"))
    )
    (net (code "44") (name "Net-(U2-G1)") (class "Default")
      (node (ref "R12") (pin "1") (pinfunction "1_1") (pintype "passive"))
      (node (ref "U2") (pin "2") (pinfunction "G1_2") (pintype "passive"))
    )
    (net (code "45") (name "Net-(U2-G2)") (class "Default")
      (node (ref "R18") (pin "1") (pinfunction "1_1") (pintype "passive"))
      (node (ref "U2") (pin "4") (pinfunction "G2_4") (pintype "passive"))
    )
    (net (code "46") (name "Net-(U2-S2)") (class "Default")
      (node (ref "C4") (pin "1") (pinfunction "1_1") (pintype "passive"))
      (node (ref "R15") (pin "2") (pinfunction "2_2") (pintype "passive"))
      (node (ref "U2") (pin "3") (pinfunction "S2_3") (pintype "passive"))
    )
    (net (code "47") (name "Net-(U3B-IN-)") (class "Default")
      (node (ref "R19") (pin "2") (pinfunction "2_2") (pintype "passive"))
      (node (ref "R20") (pin "1") (pinfunction "1_1") (pintype "passive"))
      (node (ref "U3") (pin "6") (pinfunction "IN-_6") (pintype "input"))
    )
    (net (code "48") (name "Net-(U4-OUT)") (class "Default")
      (node (ref "C8") (pin "1") (pinfunction "1_1") (pintype "passive"))
      (node (ref "C9") (pin "2") (pinfunction "2_2") (pintype "passive"))
      (node (ref "F1") (pin "1") (pinfunction "1_1") (pintype "passive"))
      (node (ref "R25") (pin "2") (pinfunction "2_2") (pintype "passive"))
      (node (ref "R36") (pin "2") (pinfunction "2_2") (pintype "passive"))
      (node (ref "U4") (pin "4") (pinfunction "OUT_4") (pintype "passive"))
    )
    (net (code "49") (name "Net-(U6-C1+)") (class "Default")
      (node (ref "C13") (pin "1") (pinfunction "1_1") (pintype "passive"))
      (node (ref "U6") (pin "2") (pinfunction "C1+_2") (pintype "input"))
    )
    (net (code "50") (name "Net-(U6-C1-)") (class "Default")
      (node (ref "C13") (pin "2") (pinfunction "2_2") (pintype "passive"))
      (node (ref "U6") (pin "4") (pinfunction "C1-_4") (pintype "input"))
    )
    (net (code "51") (name "Net-(U7-OUT)") (class "Default")
      (node (ref "C15") (pin "1") (pinfunction "1_1") (pintype "passive"))
      (node (ref "C16") (pin "2") (pinfunction "2_2") (pintype "passive"))
      (node (ref "F3") (pin "1") (pinfunction "1_1") (pintype "passive"))
      (node (ref "R37") (pin "2") (pinfunction "2_2") (pintype "passive"))
      (node (ref "R38") (pin "2") (pinfunction "2_2") (pintype "passive"))
      (node (ref "U7") (pin "2") (pinfunction "OUT_2") (pintype "power_in"))
    )
    (net (code "52") (name "Net-(U8-TAB)") (class "Default")
      (node (ref "C19") (pin "2") (pinfunction "2_2") (pintype "passive"))
      (node (ref "R33") (pin "1") (pinfunction "1_1") (pintype "passive"))
      (node (ref "U8") (pin "8") (pinfunction "TAB_8") (pintype "passive"))
    )
    (net (code "53") (name "Net-(U9-+V)") (class "Default")
      (node (ref "R32") (pin "1") (pinfunction "1_1") (pintype "passive"))
      (node (ref "U8") (pin "5") (pinfunction "OS_NUL_5") (pintype "passive"))
      (node (ref "U9") (pin "1") (pinfunction "+V_1") (pintype "passive"))
    )
    (net (code "54") (name "Net-(U10-OUT)") (class "Default")
      (node (ref "C21") (pin "2") (pinfunction "2_2") (pintype "passive"))
      (node (ref "C23") (pin "1") (pinfunction "1_1") (pintype "passive"))
      (node (ref "F5") (pin "1") (pinfunction "1_1") (pintype "passive"))
      (node (ref "R39") (pin "2") (pinfunction "2_2") (pintype "passive"))
      (node (ref "R40") (pin "2") (pinfunction "2_2") (pintype "passive"))
      (node (ref "U10") (pin "2") (pinfunction "OUT_2") (pintype "power_in"))
    )
    (net (code "55") (name "OP_OUT") (class "Default")
      (node (ref "Q1") (pin "2") (pinfunction "E_2") (pintype "passive"))
      (node (ref "Q2") (pin "2") (pinfunction "E_2") (pintype "passive"))
      (node (ref "Q9") (pin "3") (pinfunction "E_3") (pintype "passive"))
      (node (ref "R1") (pin "2") (pinfunction "2_2") (pintype "passive"))
      (node (ref "R2") (pin "2") (pinfunction "2_2") (pintype "passive"))
      (node (ref "R20") (pin "2") (pinfunction "2_2") (pintype "passive"))
    )
    (net (code "56") (name "SGND") (class "Default")
      (node (ref "C1") (pin "2") (pinfunction "2_2") (pintype "passive"))
      (node (ref "C15") (pin "2") (pinfunction "2_2") (pintype "passive"))
      (node (ref "C16") (pin "1") (pinfunction "1_1") (pintype "passive"))
      (node (ref "C17") (pin "1") (pinfunction "1_1") (pintype "passive"))
      (node (ref "C18") (pin "1") (pinfunction "1_1") (pintype "passive"))
      (node (ref "C2") (pin "2") (pinfunction "2_2") (pintype "passive"))
      (node (ref "C4") (pin "2") (pinfunction "2_2") (pintype "passive"))
      (node (ref "F4") (pin "2") (pinfunction "2_2") (pintype "passive"))
      (node (ref "Q7") (pin "2") (pinfunction "E_2") (pintype "passive"))
      (node (ref "Q8") (pin "2") (pinfunction "E_2") (pintype "passive"))
      (node (ref "R14") (pin "1") (pinfunction "1_1") (pintype "passive"))
      (node (ref "R16") (pin "2") (pinfunction "2_2") (pintype "passive"))
      (node (ref "R22") (pin "1") (pinfunction "1_1") (pintype "passive"))
      (node (ref "R31") (pin "2") (pinfunction "BOT_2") (pintype "passive"))
      (node (ref "R41") (pin "1") (pinfunction "1_1") (pintype "passive"))
      (node (ref "U1") (pin "3") (pinfunction "GND_3") (pintype "passive"))
      (node (ref "U2") (pin "1") (pinfunction "S1_1") (pintype "passive"))
      (node (ref "U5") (pin "3") (pinfunction "S/R-_3") (pintype "passive"))
    )
    (net (code "57") (name "VCC_IN") (class "Default")
      (node (ref "C18") (pin "2") (pinfunction "2_2") (pintype "passive"))
      (node (ref "C24") (pin "2") (pinfunction "2_2") (pintype "passive"))
      (node (ref "C6") (pin "1") (pinfunction "1_1") (pintype "passive"))
      (node (ref "C7") (pin "2") (pinfunction "2_2") (pintype "passive"))
      (node (ref "P1") (pin "10") (pinfunction "10_10") (pintype "passive"))
      (node (ref "R35") (pin "2") (pinfunction "2_2") (pintype "passive"))
      (node (ref "U10") (pin "3") (pinfunction "IN_3") (pintype "power_in"))
      (node (ref "U4") (pin "2") (pinfunction "IN_2") (pintype "passive"))
      (node (ref "U7") (pin "3") (pinfunction "IN_3") (pintype "power_in"))
    )
    (net (code "58") (name "unconnected-(U1-NC-Pad1)") (class "Default")
      (node (ref "U1") (pin "1") (pinfunction "NC_1") (pintype "passive+no_connect"))
    )
    (net (code "59") (name "unconnected-(U1-NC-Pad8)") (class "Default")
      (node (ref "U1") (pin "8") (pinfunction "NC_8") (pintype "passive+no_connect"))
    )
    (net (code "60") (name "unconnected-(U3A-IN+-Pad3)") (class "Default")
      (node (ref "U3") (pin "3") (pinfunction "IN+_3") (pintype "input+no_connect"))
    )
    (net (code "61") (name "unconnected-(U3A-IN--Pad2)") (class "Default")
      (node (ref "U3") (pin "2") (pinfunction "IN-_2") (pintype "input+no_connect"))
    )
    (net (code "62") (name "unconnected-(U3A-OUT-Pad1)") (class "Default")
      (node (ref "U3") (pin "1") (pinfunction "OUT_1") (pintype "output+no_connect"))
    )
    (net (code "63") (name "unconnected-(U6-LV-Pad6)") (class "Default")
      (node (ref "U6") (pin "6") (pinfunction "LV_6") (pintype "input+no_connect"))
    )
    (net (code "64") (name "unconnected-(U6-NC-Pad1)") (class "Default")
      (node (ref "U6") (pin "1") (pinfunction "NC_1") (pintype "passive+no_connect"))
    )
    (net (code "65") (name "unconnected-(U6-OSC-Pad7)") (class "Default")
      (node (ref "U6") (pin "7") (pinfunction "OSC_7") (pintype "input+no_connect"))
    )
    (net (code "66") (name "unconnected-(U9-NC-Pad3)") (class "Default")
      (node (ref "U9") (pin "3") (pinfunction "NC_3") (pintype "passive+no_connect"))
    )
  )
)
